# inertial-gy91.net
KiCad netlist of a schematic drawn in Altium Designer
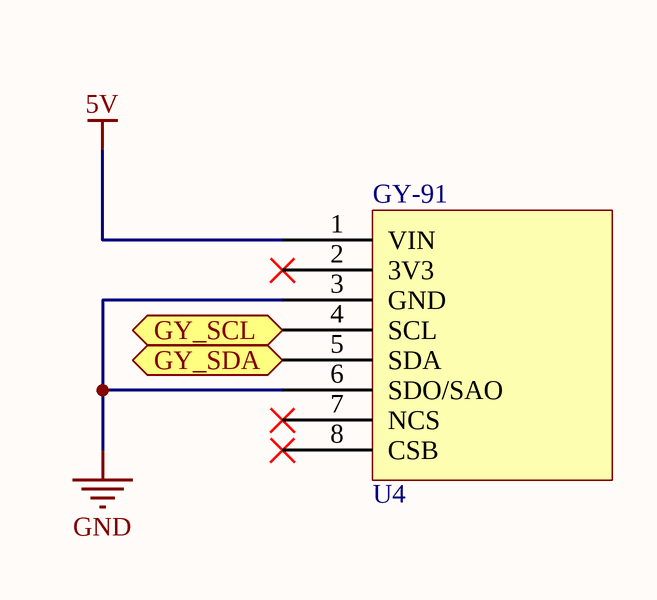
[diagram p0: inertial-gy91.SchDoc]

(export (version "E")
  (design (tool "Eeschema 10.0.6"))
  (components
    (comp (ref "U4") (value "GY-91") (footprint "GY-91") (libsource (lib "main-board") (part "GY-91")))
  )
  (nets
    (net (code "1") (name "/GY_SCL") (class "Default")
      (node (ref "U4") (pin "4") (pinfunction "SCL_4") (pintype "passive"))
    )
    (net (code "2") (name "/GY_SDA") (class "Default")
      (node (ref "U4") (pin "5") (pinfunction "SDA_5") (pintype "passive"))
    )
    (net (code "3") (name "5V") (class "Default")
      (node (ref "U4") (pin "1") (pinfunction "VIN_1") (pintype "passive"))
    )
    (net (code "4") (name "GND") (class "Default")
      (node (ref "U4") (pin "3") (pinfunction "GND_3") (pintype "passive"))
      (node (ref "U4") (pin "6") (pinfunction "SDO/SAO_6") (pintype "passive"))
    )
    (net (code "5") (name "unconnected-(U4-3V3-Pad2)") (class "Default")
      (node (ref "U4") (pin "2") (pinfunction "3V3_2") (pintype "passive+no_connect"))
    )
    (net (code "6") (name "unconnected-(U4-CSB-Pad8)") (class "Default")
      (node (ref "U4") (pin "8") (pinfunction "CSB_8") (pintype "passive+no_connect"))
    )
    (net (code "7") (name "unconnected-(U4-NCS-Pad7)") (class "Default")
      (node (ref "U4") (pin "7") (pinfunction "NCS_7") (pintype "passive+no_connect"))
    )
  )
)
